# comm_connector.net
KiCad netlist of a schematic drawn in Altium Designer
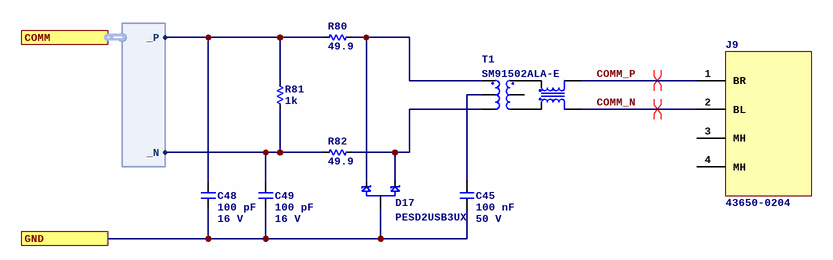
[diagram p0: comm_connector.SchDoc]

(export (version "E")
  (design (tool "Eeschema 10.0.6"))
  (components
    (comp (ref "C45")
      (value "CL05B104KB54PNC")
      (footprint "C0402")
      (fields
        (field (name "CAPACITANCE") "100 nF")
        (field (name "MANUFACTURER") "Samsung Electro-Mechanics")
        (field (name "VOLTAGE RATING") "50 V")
      )
      (libsource (lib "database") (part "__template_cap"))
    )
    (comp (ref "C48")
      (value "0402YA101JAT2A")
      (footprint "C0402")
      (fields
        (field (name "CAPACITANCE") "100 pF")
        (field (name "MANUFACTURER") "Kyocera AVX")
        (field (name "VOLTAGE RATING") "16 V")
      )
      (libsource (lib "database") (part "__template_cap"))
    )
    (comp (ref "C49")
      (value "0402YA101JAT2A")
      (footprint "C0402")
      (fields
        (field (name "CAPACITANCE") "100 pF")
        (field (name "MANUFACTURER") "Kyocera AVX")
        (field (name "VOLTAGE RATING") "16 V")
      )
      (libsource (lib "database") (part "__template_cap"))
    )
    (comp (ref "D17")
      (value "PESD2USB3UX")
      (footprint "3SOT23")
      (description "DIODE ESD USB SOT-23")
      (fields (field (name "MANUFACTURER") "Nexperia USA Inc."))
      (libsource (lib "database") (part "PESD2USB3UX"))
    )
    (comp (ref "J9")
      (value "43650-0204")
      (footprint "MOLEX_MICROFIT_0436500204")
      (description "Rectangular Power Connector, 2 Contact(s), Male, Solder Terminal, Receptacle")
      (fields (field (name "MANUFACTURER") "Molex"))
      (libsource (lib "database") (part "43650-0204"))
    )
    (comp (ref "R80")
      (value "49.9")
      (footprint "R0402")
      (fields
        (field (name "MANUFACTURER PART NUMBER") "0402WGF499JTCE")
        (field (name "MANUFACTURER") "UNI-ROYAL(Uniroyal Elec)")
        (field (name "TOLERANCE") "1%")
      )
      (libsource (lib "database") (part "__template_resistor"))
    )
    (comp (ref "R81")
      (value "1k")
      (footprint "R0603")
      (fields
        (field (name "MANUFACTURER PART NUMBER") "HP03W5F1001T5E")
        (field (name "MANUFACTURER") "UNI-ROYAL(Uniroyal Elec)")
        (field (name "TOLERANCE") "1%")
      )
      (libsource (lib "database") (part "__template_resistor"))
    )
    (comp (ref "R82")
      (value "49.9")
      (footprint "R0402")
      (fields
        (field (name "MANUFACTURER PART NUMBER") "0402WGF499JTCE")
        (field (name "MANUFACTURER") "UNI-ROYAL(Uniroyal Elec)")
        (field (name "TOLERANCE") "1%")
      )
      (libsource (lib "database") (part "__template_resistor"))
    )
    (comp (ref "T1")
      (value "SM91502ALA-E")
      (footprint "BOURNS_SM91502")
      (description "200ÂµH LAN Pulse Transformer 1CT:1CT Surface Mount")
      (fields (field (name "MANUFACTURER") "Bourns Inc."))
      (libsource (lib "database") (part "SM91502ALA-E"))
    )
  )
  (nets
    (net (code "2") (name "/COMM_N") (class "Default")
      (node (ref "J9") (pin "2") (pinfunction "BL_2") (pintype "passive"))
      (node (ref "T1") (pin "4") (pinfunction "4_4") (pintype "passive"))
    )
    (net (code "3") (name "/COMM_P") (class "Default")
      (node (ref "J9") (pin "1") (pinfunction "BR_1") (pintype "passive"))
      (node (ref "T1") (pin "6") (pinfunction "6_6") (pintype "passive"))
    )
    (net (code "4") (name "/GND") (class "Default")
      (node (ref "C45") (pin "2") (pintype "passive"))
      (node (ref "C48") (pin "2") (pintype "passive"))
      (node (ref "C49") (pin "2") (pintype "passive"))
      (node (ref "D17") (pin "3") (pintype "passive"))
    )
    (net (code "6") (name "Net-(C45-Pad1)") (class "Default")
      (node (ref "C45") (pin "1") (pintype "passive"))
      (node (ref "T1") (pin "2") (pinfunction "2_2") (pintype "passive"))
    )
    (net (code "7") (name "Net-(C48-Pad1)") (class "Default")
      (node (ref "C48") (pin "1") (pintype "passive"))
      (node (ref "R80") (pin "1") (pintype "passive"))
      (node (ref "R81") (pin "2") (pintype "passive"))
    )
    (net (code "8") (name "Net-(C49-Pad1)") (class "Default")
      (node (ref "C49") (pin "1") (pintype "passive"))
      (node (ref "R81") (pin "1") (pintype "passive"))
      (node (ref "R82") (pin "1") (pintype "passive"))
    )
    (net (code "9") (name "Net-(D17-Pad1)") (class "Default")
      (node (ref "D17") (pin "1") (pintype "passive"))
      (node (ref "R82") (pin "2") (pintype "passive"))
      (node (ref "T1") (pin "3") (pinfunction "3_3") (pintype "passive"))
    )
    (net (code "10") (name "Net-(D17-Pad2)") (class "Default")
      (node (ref "D17") (pin "2") (pintype "passive"))
      (node (ref "R80") (pin "2") (pintype "passive"))
      (node (ref "T1") (pin "1") (pinfunction "1_1") (pintype "passive"))
    )
    (net (code "11") (name "unconnected-(J9-MH-Pad3)") (class "Default")
      (node (ref "J9") (pin "3") (pinfunction "MH_3") (pintype "passive"))
    )
    (net (code "12") (name "unconnected-(J9-MH-Pad4)") (class "Default")
      (node (ref "J9") (pin "4") (pinfunction "MH_4") (pintype "passive"))
    )
    (net (code "13") (name "unconnected-(T1-Pad5)") (class "Default")
      (node (ref "T1") (pin "5") (pinfunction "5_5") (pintype "passive"))
    )
  )
)
